# SIRA_Rev1.net
KiCad netlist of a schematic drawn in Altium Designer
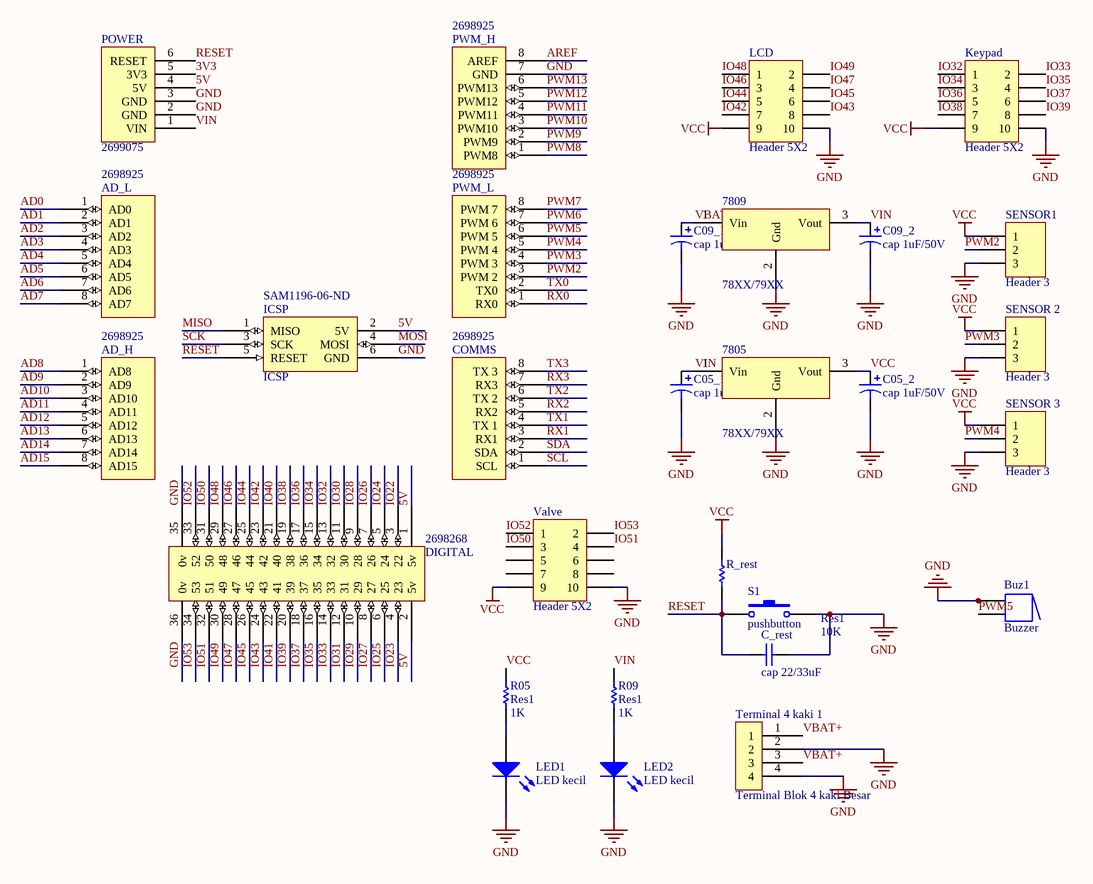
[diagram p0: SIRA_Rev1.SchDoc]

(export (version "E")
  (design (tool "Eeschema 10.0.6"))
  (components
    (comp (ref "7805")
      (value "78XX/79XX")
      (footprint "78XX/79XX")
      (libsource (lib "agfa other components") (part "7805/7809/7812/7905/7909/7912"))
    )
    (comp (ref "7809")
      (value "78XX/79XX")
      (footprint "78XX/79XX")
      (libsource (lib "agfa other components") (part "7805/7809/7812/7905/7909/7912"))
    )
    (comp (ref "AD_H")
      (value "AD_H")
      (footprint "Header 8x1 8.5mm")
      (fields (field (name "SUPPLIER PART NUMBER 4") "2698925"))
      (libsource (lib "Header") (part "AD_H"))
    )
    (comp (ref "AD_L")
      (value "AD_L")
      (footprint "Header 8x1 8.5mm")
      (fields (field (name "SUPPLIER PART NUMBER 5") "2698925"))
      (libsource (lib "Header") (part "AD_L"))
    )
    (comp (ref "Buz1")
      (value "Buzzer")
      (footprint "ABSM-1574")
      (description "Magnetic Transducer Buzzer")
      (fields (field (name "PUBLISHER") "Altium Limited"))
      (libsource (lib "Miscellaneous Devices") (part "Buzzer"))
    )
    (comp (ref "C05_1")
      (value "cap 1uF/50V")
      (footprint "cap 1uF/50V")
      (libsource (lib "agfa other components") (part "cap 1uF/50V"))
    )
    (comp (ref "C05_2")
      (value "cap 1uF/50V")
      (footprint "cap 1uF/50V")
      (libsource (lib "agfa other components") (part "cap 1uF/50V"))
    )
    (comp (ref "C09_1")
      (value "cap 1uF/50V")
      (footprint "cap 1uF/50V")
      (libsource (lib "agfa other components") (part "cap 1uF/50V"))
    )
    (comp (ref "C09_2")
      (value "cap 1uF/50V")
      (footprint "cap 1uF/50V")
      (libsource (lib "agfa other components") (part "cap 1uF/50V"))
    )
    (comp (ref "COMMS")
      (value "Communication")
      (footprint "Header 8x1 8.5mm")
      (fields (field (name "SUPPLIER PART NUMBER 4") "2698925"))
      (libsource (lib "Header") (part "Communication"))
    )
    (comp (ref "C_rest")
      (value "cap 22/33uF")
      (footprint "cap 22/33uF")
      (libsource (lib "agfa other components") (part "cap 22/33uF"))
    )
    (comp (ref "DIGITAL")
      (value "IO_36")
      (footprint "HEADER 36X 8MM")
      (fields (field (name "SUPPLIER PART NUMBER 5") "2698268"))
      (libsource (lib "Header") (part "IO_36"))
    )
    (comp (ref "ICSP")
      (value "ICSP")
      (footprint "ICSP")
      (fields (field (name "SUPPLIER PART NUMBER 5") "SAM1196-06-ND"))
      (libsource (lib "Header") (part "ICSP"))
    )
    (comp (ref "Keypad")
      (value "Header 5X2")
      (footprint "HDR2X5")
      (description "Header, 5-Pin, Dual row")
      (fields (field (name "PUBLISHER") "Altium Limited"))
      (libsource (lib "Miscellaneous Connectors") (part "Header 5X2"))
    )
    (comp (ref "LCD")
      (value "Header 5X2")
      (footprint "HDR2X5")
      (description "Header, 5-Pin, Dual row")
      (fields (field (name "PUBLISHER") "Altium Limited"))
      (libsource (lib "Miscellaneous Connectors") (part "Header 5X2"))
    )
    (comp (ref "LED1")
      (value "LED kecil")
      (footprint "LED kecil")
      (libsource (lib "agfa other components") (part "LED kecil"))
    )
    (comp (ref "LED2")
      (value "LED kecil")
      (footprint "LED kecil")
      (libsource (lib "agfa other components") (part "LED kecil"))
    )
    (comp (ref "POWER")
      (value "POWER")
      (footprint "Header 6x1 8.5mm")
      (fields (field (name "SUPPLIER PART NUMBER 2") "2699075"))
      (libsource (lib "Header") (part "POWER"))
    )
    (comp (ref "PWM_H")
      (value "PWM_H")
      (footprint "Header 8x1 8.5mm")
      (fields (field (name "SUPPLIER PART NUMBER 4") "2698925"))
      (libsource (lib "Header") (part "PWM_H"))
    )
    (comp (ref "PWM_L")
      (value "PWM_L")
      (footprint "Header 8x1 8.5mm")
      (fields (field (name "SUPPLIER PART NUMBER 4") "2698925"))
      (libsource (lib "Header") (part "PWM_L"))
    )
    (comp (ref "R05")
      (value "Res1")
      (footprint "AXIAL-0.3")
      (description "Resistor")
      (fields (field (name "ALTIUM_VALUE") "1K") (field (name "PUBLISHER") "Altium Limited"))
      (libsource (lib "Miscellaneous Devices") (part "Res1"))
    )
    (comp (ref "R09")
      (value "Res1")
      (footprint "AXIAL-0.3")
      (description "Resistor")
      (fields (field (name "ALTIUM_VALUE") "1K") (field (name "PUBLISHER") "Altium Limited"))
      (libsource (lib "Miscellaneous Devices") (part "Res1"))
    )
    (comp (ref "R_rest")
      (value "Res1")
      (footprint "AXIAL-0.3")
      (description "Resistor")
      (fields (field (name "ALTIUM_VALUE") "10K") (field (name "PUBLISHER") "Altium Limited"))
      (libsource (lib "Miscellaneous Devices") (part "Res1"))
    )
    (comp (ref "S1")
      (value "pushbutton")
      (footprint "pushbutton")
      (libsource (lib "agfa other components") (part "pushbutton"))
    )
    (comp (ref "SENSOR 2")
      (value "Header 3")
      (footprint "HDR1X3")
      (description "Header, 3-Pin")
      (fields (field (name "PUBLISHER") "Altium Limited"))
      (libsource (lib "Miscellaneous Connectors") (part "Header 3"))
    )
    (comp (ref "SENSOR 3")
      (value "Header 3")
      (footprint "HDR1X3")
      (description "Header, 3-Pin")
      (fields (field (name "PUBLISHER") "Altium Limited"))
      (libsource (lib "Miscellaneous Connectors") (part "Header 3"))
    )
    (comp (ref "SENSOR1")
      (value "Header 3")
      (footprint "HDR1X3")
      (description "Header, 3-Pin")
      (fields (field (name "PUBLISHER") "Altium Limited"))
      (libsource (lib "Miscellaneous Connectors") (part "Header 3"))
    )
    (comp (ref "Terminal 4 kaki 1")
      (value "Terminal Blok 4 kaki Besar")
      (footprint "TERMINAL 4 KAKI")
      (libsource (lib "Library Ausiher") (part "Terminal Blok 4 kaki"))
    )
    (comp (ref "Valve")
      (value "Header 5X2")
      (footprint "HDR2X5")
      (description "Header, 5-Pin, Dual row")
      (fields (field (name "PUBLISHER") "Altium Limited"))
      (libsource (lib "Miscellaneous Connectors") (part "Header 5X2"))
    )
  )
  (nets
    (net (code "1") (name "/3V3") (class "Default")
      (node (ref "POWER") (pin "5") (pinfunction "3V3_5") (pintype "power_in"))
    )
    (net (code "2") (name "/5V") (class "Default")
      (node (ref "DIGITAL") (pin "1") (pinfunction "5v_1") (pintype "power_in"))
      (node (ref "DIGITAL") (pin "2") (pinfunction "5v_2") (pintype "power_in"))
      (node (ref "ICSP") (pin "2") (pinfunction "5V_2") (pintype "power_in"))
      (node (ref "POWER") (pin "4") (pinfunction "5V_4") (pintype "power_in"))
    )
    (net (code "3") (name "/AD0") (class "Default")
      (node (ref "AD_L") (pin "1") (pinfunction "AD0_1") (pintype "bidirectional"))
    )
    (net (code "4") (name "/AD1") (class "Default")
      (node (ref "AD_L") (pin "2") (pinfunction "AD1_2") (pintype "bidirectional"))
    )
    (net (code "5") (name "/AD2") (class "Default")
      (node (ref "AD_L") (pin "3") (pinfunction "AD2_3") (pintype "bidirectional"))
    )
    (net (code "6") (name "/AD3") (class "Default")
      (node (ref "AD_L") (pin "4") (pinfunction "AD3_4") (pintype "bidirectional"))
    )
    (net (code "7") (name "/AD4") (class "Default")
      (node (ref "AD_L") (pin "5") (pinfunction "AD4_5") (pintype "bidirectional"))
    )
    (net (code "8") (name "/AD5") (class "Default")
      (node (ref "AD_L") (pin "6") (pinfunction "AD5_6") (pintype "bidirectional"))
    )
    (net (code "9") (name "/AD6") (class "Default")
      (node (ref "AD_L") (pin "7") (pinfunction "AD6_7") (pintype "bidirectional"))
    )
    (net (code "10") (name "/AD7") (class "Default")
      (node (ref "AD_L") (pin "8") (pinfunction "AD7_8") (pintype "bidirectional"))
    )
    (net (code "11") (name "/AD8") (class "Default")
      (node (ref "AD_H") (pin "1") (pinfunction "AD8_1") (pintype "bidirectional"))
    )
    (net (code "12") (name "/AD9") (class "Default")
      (node (ref "AD_H") (pin "2") (pinfunction "AD9_2") (pintype "bidirectional"))
    )
    (net (code "13") (name "/AD10") (class "Default")
      (node (ref "AD_H") (pin "3") (pinfunction "AD10_3") (pintype "bidirectional"))
    )
    (net (code "14") (name "/AD11") (class "Default")
      (node (ref "AD_H") (pin "4") (pinfunction "AD11_4") (pintype "bidirectional"))
    )
    (net (code "15") (name "/AD12") (class "Default")
      (node (ref "AD_H") (pin "5") (pinfunction "AD12_5") (pintype "bidirectional"))
    )
    (net (code "16") (name "/AD13") (class "Default")
      (node (ref "AD_H") (pin "6") (pinfunction "AD13_6") (pintype "bidirectional"))
    )
    (net (code "17") (name "/AD14") (class "Default")
      (node (ref "AD_H") (pin "7") (pinfunction "AD14_7") (pintype "bidirectional"))
    )
    (net (code "18") (name "/AD15") (class "Default")
      (node (ref "AD_H") (pin "8") (pinfunction "AD15_8") (pintype "bidirectional"))
    )
    (net (code "19") (name "/AREF") (class "Default")
      (node (ref "PWM_H") (pin "8") (pinfunction "AREF_8") (pintype "passive"))
    )
    (net (code "20") (name "/IO22") (class "Default")
      (node (ref "DIGITAL") (pin "3") (pinfunction "22_3") (pintype "bidirectional"))
    )
    (net (code "21") (name "/IO23") (class "Default")
      (node (ref "DIGITAL") (pin "4") (pinfunction "23_4") (pintype "bidirectional"))
    )
    (net (code "22") (name "/IO24") (class "Default")
      (node (ref "DIGITAL") (pin "5") (pinfunction "24_5") (pintype "bidirectional"))
    )
    (net (code "23") (name "/IO25") (class "Default")
      (node (ref "DIGITAL") (pin "6") (pinfunction "25_6") (pintype "bidirectional"))
    )
    (net (code "24") (name "/IO26") (class "Default")
      (node (ref "DIGITAL") (pin "7") (pinfunction "26_7") (pintype "bidirectional"))
    )
    (net (code "25") (name "/IO27") (class "Default")
      (node (ref "DIGITAL") (pin "8") (pinfunction "27_8") (pintype "bidirectional"))
    )
    (net (code "26") (name "/IO28") (class "Default")
      (node (ref "DIGITAL") (pin "9") (pinfunction "28_9") (pintype "bidirectional"))
    )
    (net (code "27") (name "/IO29") (class "Default")
      (node (ref "DIGITAL") (pin "10") (pinfunction "29_10") (pintype "bidirectional"))
    )
    (net (code "28") (name "/IO30") (class "Default")
      (node (ref "DIGITAL") (pin "11") (pinfunction "30_11") (pintype "bidirectional"))
    )
    (net (code "29") (name "/IO31") (class "Default")
      (node (ref "DIGITAL") (pin "12") (pinfunction "31_12") (pintype "bidirectional"))
    )
    (net (code "30") (name "/IO32") (class "Default")
      (node (ref "DIGITAL") (pin "13") (pinfunction "32_13") (pintype "bidirectional"))
      (node (ref "Keypad") (pin "1") (pinfunction "1_1") (pintype "passive"))
    )
    (net (code "31") (name "/IO33") (class "Default")
      (node (ref "DIGITAL") (pin "14") (pinfunction "33_14") (pintype "bidirectional"))
      (node (ref "Keypad") (pin "2") (pinfunction "2_2") (pintype "passive"))
    )
    (net (code "32") (name "/IO34") (class "Default")
      (node (ref "DIGITAL") (pin "15") (pinfunction "34_15") (pintype "bidirectional"))
      (node (ref "Keypad") (pin "3") (pinfunction "3_3") (pintype "passive"))
    )
    (net (code "33") (name "/IO35") (class "Default")
      (node (ref "DIGITAL") (pin "16") (pinfunction "35_16") (pintype "bidirectional"))
      (node (ref "Keypad") (pin "4") (pinfunction "4_4") (pintype "passive"))
    )
    (net (code "34") (name "/IO36") (class "Default")
      (node (ref "DIGITAL") (pin "17") (pinfunction "36_17") (pintype "bidirectional"))
      (node (ref "Keypad") (pin "5") (pinfunction "5_5") (pintype "passive"))
    )
    (net (code "35") (name "/IO37") (class "Default")
      (node (ref "DIGITAL") (pin "18") (pinfunction "37_18") (pintype "bidirectional"))
      (node (ref "Keypad") (pin "6") (pinfunction "6_6") (pintype "passive"))
    )
    (net (code "36") (name "/IO38") (class "Default")
      (node (ref "DIGITAL") (pin "19") (pinfunction "38_19") (pintype "bidirectional"))
      (node (ref "Keypad") (pin "7") (pinfunction "7_7") (pintype "passive"))
    )
    (net (code "37") (name "/IO39") (class "Default")
      (node (ref "DIGITAL") (pin "20") (pinfunction "39_20") (pintype "bidirectional"))
      (node (ref "Keypad") (pin "8") (pinfunction "8_8") (pintype "passive"))
    )
    (net (code "38") (name "/IO40") (class "Default")
      (node (ref "DIGITAL") (pin "21") (pinfunction "40_21") (pintype "bidirectional"))
    )
    (net (code "39") (name "/IO41") (class "Default")
      (node (ref "DIGITAL") (pin "22") (pinfunction "41_22") (pintype "bidirectional"))
    )
    (net (code "40") (name "/IO42") (class "Default")
      (node (ref "DIGITAL") (pin "23") (pinfunction "42_23") (pintype "bidirectional"))
      (node (ref "LCD") (pin "7") (pinfunction "7_7") (pintype "passive"))
    )
    (net (code "41") (name "/IO43") (class "Default")
      (node (ref "DIGITAL") (pin "24") (pinfunction "43_24") (pintype "bidirectional"))
      (node (ref "LCD") (pin "8") (pinfunction "8_8") (pintype "passive"))
    )
    (net (code "42") (name "/IO44") (class "Default")
      (node (ref "DIGITAL") (pin "25") (pinfunction "44_25") (pintype "bidirectional"))
      (node (ref "LCD") (pin "5") (pinfunction "5_5") (pintype "passive"))
    )
    (net (code "43") (name "/IO45") (class "Default")
      (node (ref "DIGITAL") (pin "26") (pinfunction "45_26") (pintype "bidirectional"))
      (node (ref "LCD") (pin "6") (pinfunction "6_6") (pintype "passive"))
    )
    (net (code "44") (name "/IO46") (class "Default")
      (node (ref "DIGITAL") (pin "27") (pinfunction "46_27") (pintype "bidirectional"))
      (node (ref "LCD") (pin "3") (pinfunction "3_3") (pintype "passive"))
    )
    (net (code "45") (name "/IO47") (class "Default")
      (node (ref "DIGITAL") (pin "28") (pinfunction "47_28") (pintype "bidirectional"))
      (node (ref "LCD") (pin "4") (pinfunction "4_4") (pintype "passive"))
    )
    (net (code "46") (name "/IO48") (class "Default")
      (node (ref "DIGITAL") (pin "29") (pinfunction "48_29") (pintype "bidirectional"))
      (node (ref "LCD") (pin "1") (pinfunction "1_1") (pintype "passive"))
    )
    (net (code "47") (name "/IO49") (class "Default")
      (node (ref "DIGITAL") (pin "30") (pinfunction "49_30") (pintype "bidirectional"))
      (node (ref "LCD") (pin "2") (pinfunction "2_2") (pintype "passive"))
    )
    (net (code "48") (name "/IO50") (class "Default")
      (node (ref "DIGITAL") (pin "31") (pinfunction "50_31") (pintype "bidirectional"))
      (node (ref "Valve") (pin "3") (pinfunction "3_3") (pintype "passive"))
    )
    (net (code "49") (name "/IO51") (class "Default")
      (node (ref "DIGITAL") (pin "32") (pinfunction "51_32") (pintype "bidirectional"))
      (node (ref "Valve") (pin "4") (pinfunction "4_4") (pintype "passive"))
    )
    (net (code "50") (name "/IO52") (class "Default")
      (node (ref "DIGITAL") (pin "33") (pinfunction "52_33") (pintype "bidirectional"))
      (node (ref "Valve") (pin "1") (pinfunction "1_1") (pintype "passive"))
    )
    (net (code "51") (name "/IO53") (class "Default")
      (node (ref "DIGITAL") (pin "34") (pinfunction "53_34") (pintype "bidirectional"))
      (node (ref "Valve") (pin "2") (pinfunction "2_2") (pintype "passive"))
    )
    (net (code "52") (name "/MISO") (class "Default")
      (node (ref "ICSP") (pin "1") (pinfunction "MISO_1") (pintype "bidirectional"))
    )
    (net (code "53") (name "/MOSI") (class "Default")
      (node (ref "ICSP") (pin "4") (pinfunction "MOSI_4") (pintype "bidirectional"))
    )
    (net (code "54") (name "/PWM2") (class "Default")
      (node (ref "PWM_L") (pin "3") (pinfunction "PWM_2_3") (pintype "bidirectional"))
      (node (ref "SENSOR1") (pin "2") (pinfunction "2_2") (pintype "passive"))
    )
    (net (code "55") (name "/PWM3") (class "Default")
      (node (ref "PWM_L") (pin "4") (pinfunction "PWM_3_4") (pintype "bidirectional"))
      (node (ref "SENSOR 2") (pin "2") (pinfunction "2_2") (pintype "passive"))
    )
    (net (code "56") (name "/PWM4") (class "Default")
      (node (ref "PWM_L") (pin "5") (pinfunction "PWM_4_5") (pintype "bidirectional"))
      (node (ref "SENSOR 3") (pin "2") (pinfunction "2_2") (pintype "passive"))
    )
    (net (code "57") (name "/PWM5") (class "Default")
      (node (ref "Buz1") (pin "2") (pinfunction "2_2") (pintype "passive"))
      (node (ref "Buz1") (pin "2A") (pinfunction "2A_2A") (pintype "passive"))
      (node (ref "PWM_L") (pin "6") (pinfunction "PWM_5_6") (pintype "bidirectional"))
    )
    (net (code "58") (name "/PWM6") (class "Default")
      (node (ref "PWM_L") (pin "7") (pinfunction "PWM_6_7") (pintype "bidirectional"))
    )
    (net (code "59") (name "/PWM7") (class "Default")
      (node (ref "PWM_L") (pin "8") (pinfunction "PWM_7_8") (pintype "bidirectional"))
    )
    (net (code "60") (name "/PWM8") (class "Default")
      (node (ref "PWM_H") (pin "1") (pinfunction "PWM8_1") (pintype "bidirectional"))
    )
    (net (code "61") (name "/PWM9") (class "Default")
      (node (ref "PWM_H") (pin "2") (pinfunction "PWM9_2") (pintype "bidirectional"))
    )
    (net (code "62") (name "/PWM10") (class "Default")
      (node (ref "PWM_H") (pin "3") (pinfunction "PWM10_3") (pintype "bidirectional"))
    )
    (net (code "63") (name "/PWM11") (class "Default")
      (node (ref "PWM_H") (pin "4") (pinfunction "PWM11_4") (pintype "bidirectional"))
    )
    (net (code "64") (name "/PWM12") (class "Default")
      (node (ref "PWM_H") (pin "5") (pinfunction "PWM12_5") (pintype "bidirectional"))
    )
    (net (code "65") (name "/PWM13") (class "Default")
      (node (ref "PWM_H") (pin "6") (pinfunction "PWM13_6") (pintype "bidirectional"))
    )
    (net (code "66") (name "/RESET") (class "Default")
      (node (ref "C_rest") (pin "2") (pinfunction "2_2") (pintype "passive"))
      (node (ref "ICSP") (pin "5") (pinfunction "RESET_5") (pintype "input"))
      (node (ref "POWER") (pin "6") (pinfunction "RESET_6") (pintype "passive"))
      (node (ref "R_rest") (pin "1") (pinfunction "1_1") (pintype "passive"))
      (node (ref "S1") (pin "1") (pinfunction "1_1") (pintype "passive"))
    )
    (net (code "67") (name "/RX0") (class "Default")
      (node (ref "PWM_L") (pin "1") (pinfunction "RX0_1") (pintype "bidirectional"))
    )
    (net (code "68") (name "/RX1") (class "Default")
      (node (ref "COMMS") (pin "3") (pinfunction "RX1_3") (pintype "bidirectional"))
    )
    (net (code "69") (name "/RX2") (class "Default")
      (node (ref "COMMS") (pin "5") (pinfunction "RX2_5") (pintype "bidirectional"))
    )
    (net (code "70") (name "/RX3") (class "Default")
      (node (ref "COMMS") (pin "7") (pinfunction "RX3_7") (pintype "bidirectional"))
    )
    (net (code "71") (name "/SCK") (class "Default")
      (node (ref "ICSP") (pin "3") (pinfunction "SCK_3") (pintype "bidirectional"))
    )
    (net (code "72") (name "/SCL") (class "Default")
      (node (ref "COMMS") (pin "1") (pinfunction "SCL_1") (pintype "bidirectional"))
    )
    (net (code "73") (name "/SDA") (class "Default")
      (node (ref "COMMS") (pin "2") (pinfunction "SDA_2") (pintype "bidirectional"))
    )
    (net (code "74") (name "/TX0") (class "Default")
      (node (ref "PWM_L") (pin "2") (pinfunction "TX0_2") (pintype "bidirectional"))
    )
    (net (code "75") (name "/TX1") (class "Default")
      (node (ref "COMMS") (pin "4") (pinfunction "TX_1_4") (pintype "bidirectional"))
    )
    (net (code "76") (name "/TX2") (class "Default")
      (node (ref "COMMS") (pin "6") (pinfunction "TX_2_6") (pintype "bidirectional"))
    )
    (net (code "77") (name "/TX3") (class "Default")
      (node (ref "COMMS") (pin "8") (pinfunction "TX_3_8") (pintype "bidirectional"))
    )
    (net (code "78") (name "/VBAT+") (class "Default")
      (node (ref "7809") (pin "1") (pinfunction "Vin_1") (pintype "passive"))
      (node (ref "C09_1") (pin "1") (pinfunction "1_1") (pintype "passive"))
      (node (ref "Terminal 4 kaki 1") (pin "1") (pinfunction "1_1") (pintype "passive"))
      (node (ref "Terminal 4 kaki 1") (pin "3") (pinfunction "3_3") (pintype "passive"))
    )
    (net (code "79") (name "/VIN") (class "Default")
      (node (ref "7805") (pin "1") (pinfunction "Vin_1") (pintype "passive"))
      (node (ref "7809") (pin "3") (pinfunction "Vout_3") (pintype "passive"))
      (node (ref "C05_1") (pin "1") (pinfunction "1_1") (pintype "passive"))
      (node (ref "C09_2") (pin "1") (pinfunction "1_1") (pintype "passive"))
      (node (ref "POWER") (pin "1") (pinfunction "VIN_1") (pintype "power_in"))
      (node (ref "R09") (pin "2") (pinfunction "2_2") (pintype "passive"))
    )
    (net (code "80") (name "GND") (class "Default")
      (node (ref "7805") (pin "2") (pinfunction "Gnd_2") (pintype "passive"))
      (node (ref "7809") (pin "2") (pinfunction "Gnd_2") (pintype "passive"))
      (node (ref "Buz1") (pin "1") (pinfunction "1_1") (pintype "passive"))
      (node (ref "Buz1") (pin "1A") (pinfunction "1A_1A") (pintype "passive"))
      (node (ref "C05_1") (pin "2") (pinfunction "2_2") (pintype "passive"))
      (node (ref "C05_2") (pin "2") (pinfunction "2_2") (pintype "passive"))
      (node (ref "C09_1") (pin "2") (pinfunction "2_2") (pintype "passive"))
      (node (ref "C09_2") (pin "2") (pinfunction "2_2") (pintype "passive"))
      (node (ref "C_rest") (pin "1") (pinfunction "1_1") (pintype "passive"))
      (node (ref "DIGITAL") (pin "35") (pinfunction "0v_35") (pintype "power_in"))
      (node (ref "DIGITAL") (pin "36") (pinfunction "0v_36") (pintype "power_in"))
      (node (ref "ICSP") (pin "6") (pinfunction "GND_6") (pintype "power_in"))
      (node (ref "Keypad") (pin "10") (pinfunction "10_10") (pintype "passive"))
      (node (ref "LCD") (pin "10") (pinfunction "10_10") (pintype "passive"))
      (node (ref "LED1") (pin "2") (pinfunction "K_2") (pintype "passive"))
      (node (ref "LED2") (pin "2") (pinfunction "K_2") (pintype "passive"))
      (node (ref "POWER") (pin "2") (pinfunction "GND_2") (pintype "power_in"))
      (node (ref "POWER") (pin "3") (pinfunction "GND_3") (pintype "power_in"))
      (node (ref "PWM_H") (pin "7") (pinfunction "GND_7") (pintype "power_in"))
      (node (ref "S1") (pin "2") (pinfunction "2_2") (pintype "passive"))
      (node (ref "SENSOR 2") (pin "3") (pinfunction "3_3") (pintype "passive"))
      (node (ref "SENSOR 3") (pin "3") (pinfunction "3_3") (pintype "passive"))
      (node (ref "SENSOR1") (pin "3") (pinfunction "3_3") (pintype "passive"))
      (node (ref "Terminal 4 kaki 1") (pin "2") (pinfunction "2_2") (pintype "passive"))
      (node (ref "Terminal 4 kaki 1") (pin "4") (pinfunction "4_4") (pintype "passive"))
      (node (ref "Valve") (pin "10") (pinfunction "10_10") (pintype "passive"))
    )
    (net (code "81") (name "Net-(LED1-A)") (class "Default")
      (node (ref "LED1") (pin "1") (pinfunction "A_1") (pintype "passive"))
      (node (ref "R05") (pin "1") (pinfunction "1_1") (pintype "passive"))
    )
    (net (code "82") (name "Net-(LED2-A)") (class "Default")
      (node (ref "LED2") (pin "1") (pinfunction "A_1") (pintype "passive"))
      (node (ref "R09") (pin "1") (pinfunction "1_1") (pintype "passive"))
    )
    (net (code "83") (name "VCC") (class "Default")
      (node (ref "7805") (pin "3") (pinfunction "Vout_3") (pintype "passive"))
      (node (ref "C05_2") (pin "1") (pinfunction "1_1") (pintype "passive"))
      (node (ref "Keypad") (pin "9") (pinfunction "9_9") (pintype "passive"))
      (node (ref "LCD") (pin "9") (pinfunction "9_9") (pintype "passive"))
      (node (ref "R05") (pin "2") (pinfunction "2_2") (pintype "passive"))
      (node (ref "R_rest") (pin "2") (pinfunction "2_2") (pintype "passive"))
      (node (ref "SENSOR 2") (pin "1") (pinfunction "1_1") (pintype "passive"))
      (node (ref "SENSOR 3") (pin "1") (pinfunction "1_1") (pintype "passive"))
      (node (ref "SENSOR1") (pin "1") (pinfunction "1_1") (pintype "passive"))
      (node (ref "Valve") (pin "9") (pinfunction "9_9") (pintype "passive"))
    )
    (net (code "84") (name "unconnected-(Valve-Pad5)") (class "Default")
      (node (ref "Valve") (pin "5") (pinfunction "5_5") (pintype "passive"))
    )
    (net (code "85") (name "unconnected-(Valve-Pad6)") (class "Default")
      (node (ref "Valve") (pin "6") (pinfunction "6_6") (pintype "passive"))
    )
    (net (code "86") (name "unconnected-(Valve-Pad7)") (class "Default")
      (node (ref "Valve") (pin "7") (pinfunction "7_7") (pintype "passive"))
    )
    (net (code "87") (name "unconnected-(Valve-Pad8)") (class "Default")
      (node (ref "Valve") (pin "8") (pinfunction "8_8") (pintype "passive"))
    )
  )
)
